# TSL2561_Luminosity_Sensor_BOB.net
KiCad netlist of a schematic drawn in EAGLE
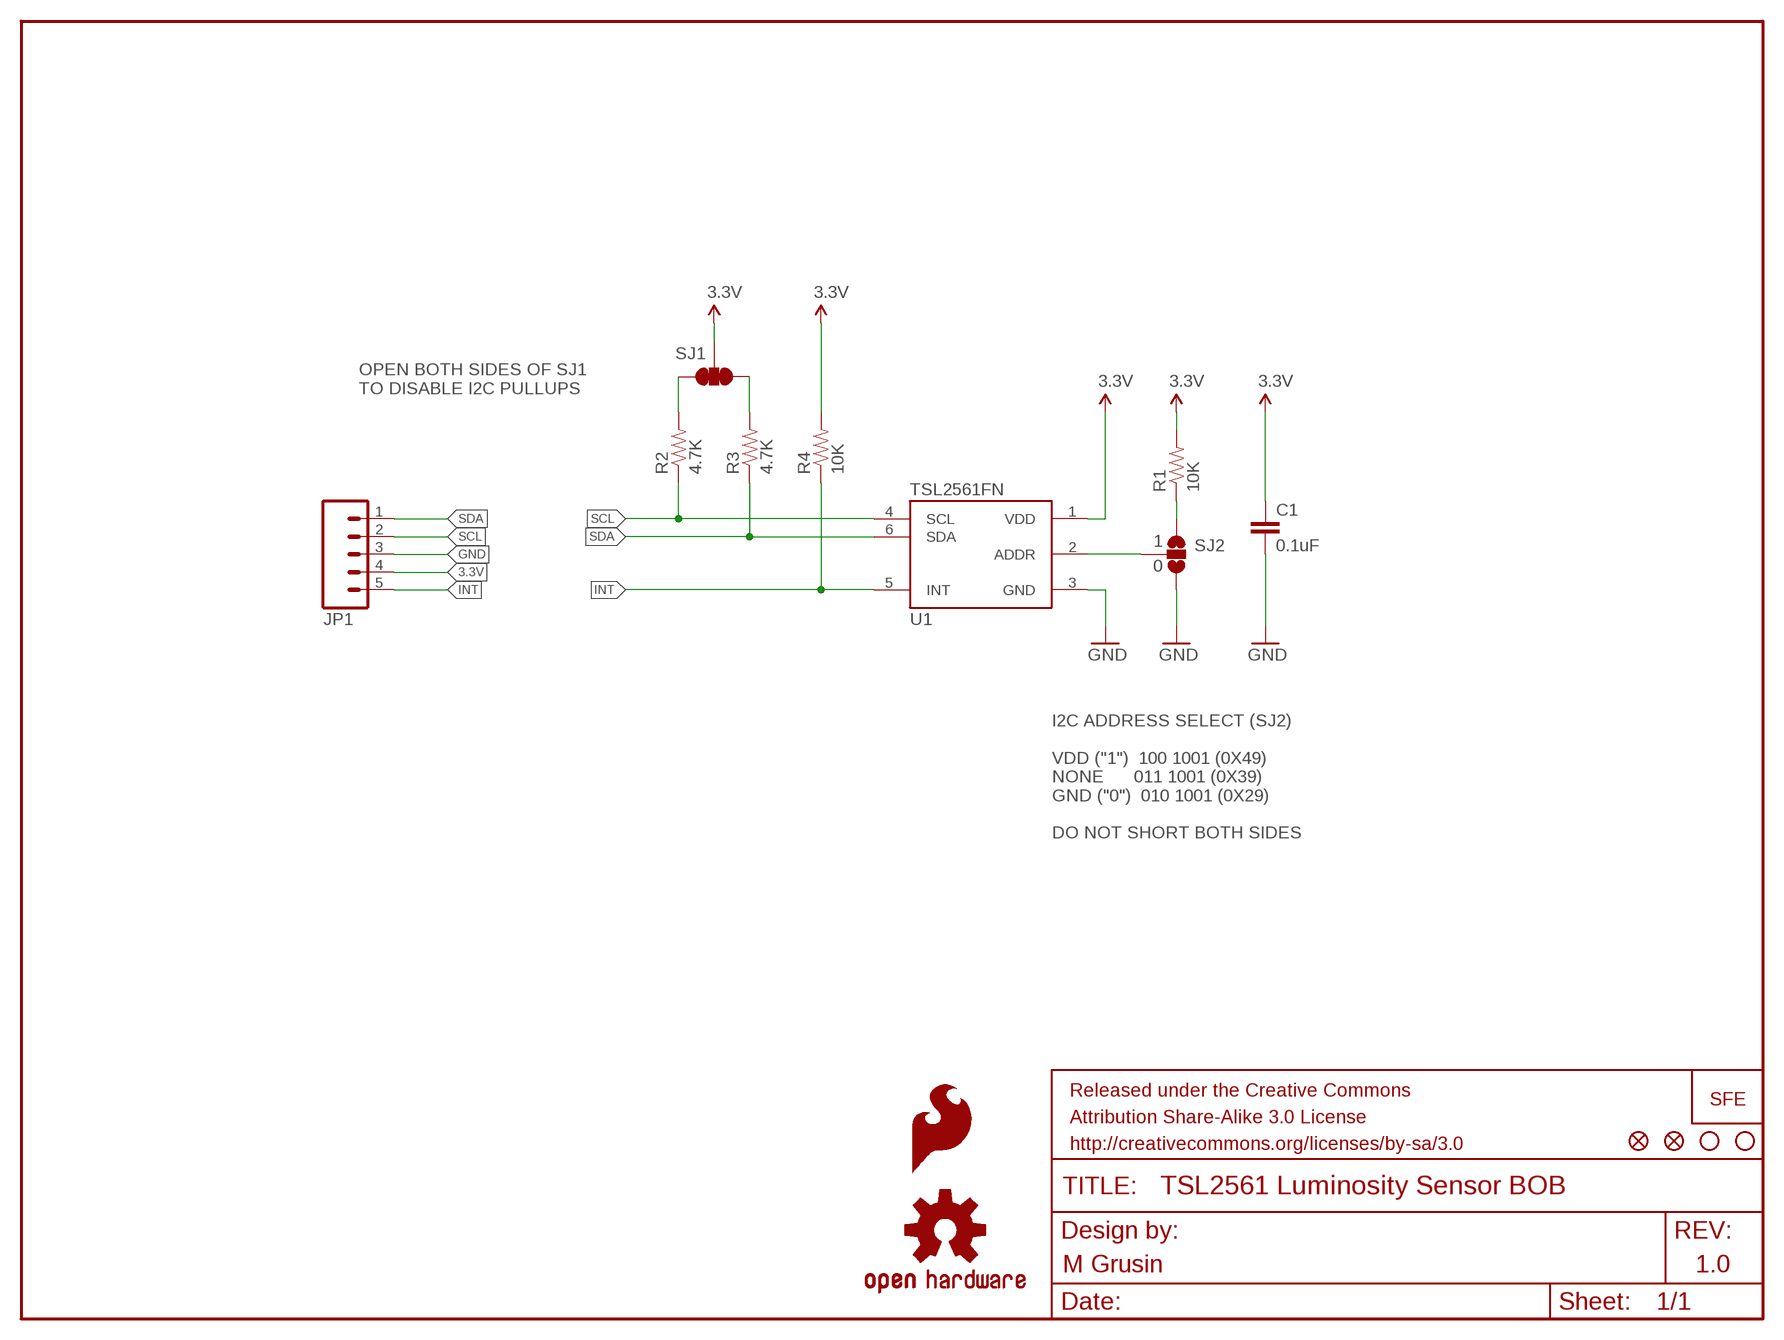
[diagram p0: schematic, sheet 1]

(export (version "E")
  (design (tool "Eeschema 10.0.6"))
  (components
    (comp (ref "C1")
      (value "0.1uF")
      (footprint "eagle-import:0603-CAP")
      (libsource (lib "eagle-import") (part "CAP0603-CAP"))
    )
    (comp (ref "FID1")
      (value "FIDUCIALUFIDUCIAL")
      (footprint "eagle-import:MICRO-FIDUCIAL")
      (libsource (lib "eagle-import") (part "FIDUCIALUFIDUCIAL"))
    )
    (comp (ref "FID2")
      (value "FIDUCIALUFIDUCIAL")
      (footprint "eagle-import:MICRO-FIDUCIAL")
      (libsource (lib "eagle-import") (part "FIDUCIALUFIDUCIAL"))
    )
    (comp (ref "FRAME1")
      (value "FRAME-LETTER")
      (footprint "eagle-import:CREATIVE_COMMONS")
      (libsource (lib "eagle-import") (part "FRAME-LETTER"))
    )
    (comp (ref "JP1")
      (value "M05_ROUNDONLY_NOSILK")
      (footprint "eagle-import:1X05_ROUNDONLY_NOSILK")
      (libsource (lib "eagle-import") (part "M05_ROUNDONLY_NOSILK"))
    )
    (comp (ref "LOGO1")
      (value "OSHW-LOGOS")
      (footprint "eagle-import:OSHW-LOGO-S")
      (libsource (lib "eagle-import") (part "OSHW-LOGOS"))
    )
    (comp (ref "LOGO2")
      (value "LOGO-SFENW2")
      (footprint "eagle-import:SFE-NEW-WEB")
      (libsource (lib "eagle-import") (part "LOGO-SFENW2"))
    )
    (comp (ref "LOGO3")
      (value "SFE_LOGO_FLAME.1_INCH")
      (footprint "eagle-import:SFE_LOGO_FLAME_.1")
      (libsource (lib "eagle-import") (part "SFE_LOGO_FLAME.1_INCH"))
    )
    (comp (ref "R1")
      (value "10K")
      (footprint "eagle-import:0603-RES")
      (libsource (lib "eagle-import") (part "RESISTOR0603"))
    )
    (comp (ref "R2")
      (value "4.7K")
      (footprint "eagle-import:0603-RES")
      (libsource (lib "eagle-import") (part "RESISTOR0603"))
    )
    (comp (ref "R3")
      (value "4.7K")
      (footprint "eagle-import:0603-RES")
      (libsource (lib "eagle-import") (part "RESISTOR0603"))
    )
    (comp (ref "R4")
      (value "10K")
      (footprint "eagle-import:0603-RES")
      (libsource (lib "eagle-import") (part "RESISTOR0603"))
    )
    (comp (ref "SJ1")
      (value "SOLDERJUMPER_2WAYPASTE1&2&3")
      (footprint "eagle-import:SJ_3_PASTE1&2&3")
      (libsource (lib "eagle-import") (part "SOLDERJUMPER_2WAYPASTE1&2&3"))
    )
    (comp (ref "SJ2")
      (value "SOLDERJUMPER_2WAYS")
      (footprint "eagle-import:SJ_3")
      (libsource (lib "eagle-import") (part "SOLDERJUMPER_2WAYS"))
    )
    (comp (ref "STANDOFF1")
      (value "STAND-OFF")
      (footprint "eagle-import:STAND-OFF")
      (libsource (lib "eagle-import") (part "STAND-OFF"))
    )
    (comp (ref "STANDOFF2")
      (value "STAND-OFF")
      (footprint "eagle-import:STAND-OFF")
      (libsource (lib "eagle-import") (part "STAND-OFF"))
    )
    (comp (ref "U1")
      (value "TSL2561FN")
      (footprint "eagle-import:FN-6")
      (libsource (lib "eagle-import") (part "TSL2561FN"))
    )
  )
  (nets
    (net (code "1") (name "3.3V") (class "Default")
      (node (ref "C1") (pin "1") (pinfunction "1_1") (pintype "passive"))
      (node (ref "JP1") (pin "4") (pinfunction "4_4") (pintype "passive"))
      (node (ref "R1") (pin "2") (pinfunction "2_2") (pintype "passive"))
      (node (ref "R4") (pin "2") (pinfunction "2_2") (pintype "passive"))
      (node (ref "SJ1") (pin "2") (pinfunction "2_2") (pintype "passive"))
      (node (ref "U1") (pin "1") (pinfunction "VDD_1") (pintype "power_in"))
    )
    (net (code "2") (name "GND") (class "Default")
      (node (ref "C1") (pin "2") (pinfunction "2_2") (pintype "passive"))
      (node (ref "JP1") (pin "3") (pinfunction "3_3") (pintype "passive"))
      (node (ref "SJ2") (pin "3") (pinfunction "3_3") (pintype "passive"))
      (node (ref "U1") (pin "3") (pinfunction "GND_3") (pintype "power_in"))
    )
    (net (code "3") (name "INT") (class "Default")
      (node (ref "JP1") (pin "5") (pinfunction "5_5") (pintype "passive"))
      (node (ref "R4") (pin "1") (pinfunction "1_1") (pintype "passive"))
      (node (ref "U1") (pin "5") (pinfunction "INT_5") (pintype "output"))
    )
    (net (code "4") (name "Net-(R1-Pad1)") (class "Default")
      (node (ref "R1") (pin "1") (pinfunction "1_1") (pintype "passive"))
      (node (ref "SJ2") (pin "1") (pinfunction "1_1") (pintype "passive"))
    )
    (net (code "5") (name "Net-(R2-Pad2)") (class "Default")
      (node (ref "R2") (pin "2") (pinfunction "2_2") (pintype "passive"))
      (node (ref "SJ1") (pin "3") (pinfunction "3_3") (pintype "passive"))
    )
    (net (code "6") (name "Net-(R3-Pad2)") (class "Default")
      (node (ref "R3") (pin "2") (pinfunction "2_2") (pintype "passive"))
      (node (ref "SJ1") (pin "1") (pinfunction "1_1") (pintype "passive"))
    )
    (net (code "7") (name "Net-(U1-ADDR)") (class "Default")
      (node (ref "SJ2") (pin "2") (pinfunction "2_2") (pintype "passive"))
      (node (ref "U1") (pin "2") (pinfunction "ADDR_2") (pintype "input"))
    )
    (net (code "8") (name "SCL") (class "Default")
      (node (ref "JP1") (pin "2") (pinfunction "2_2") (pintype "passive"))
      (node (ref "R2") (pin "1") (pinfunction "1_1") (pintype "passive"))
      (node (ref "U1") (pin "4") (pinfunction "SCL_4") (pintype "input"))
    )
    (net (code "9") (name "SDA") (class "Default")
      (node (ref "JP1") (pin "1") (pinfunction "1_1") (pintype "passive"))
      (node (ref "R3") (pin "1") (pinfunction "1_1") (pintype "passive"))
      (node (ref "U1") (pin "6") (pinfunction "SDA_6") (pintype "bidirectional"))
    )
  )
)
